# Power.net
KiCad netlist of a schematic drawn in Altium Designer
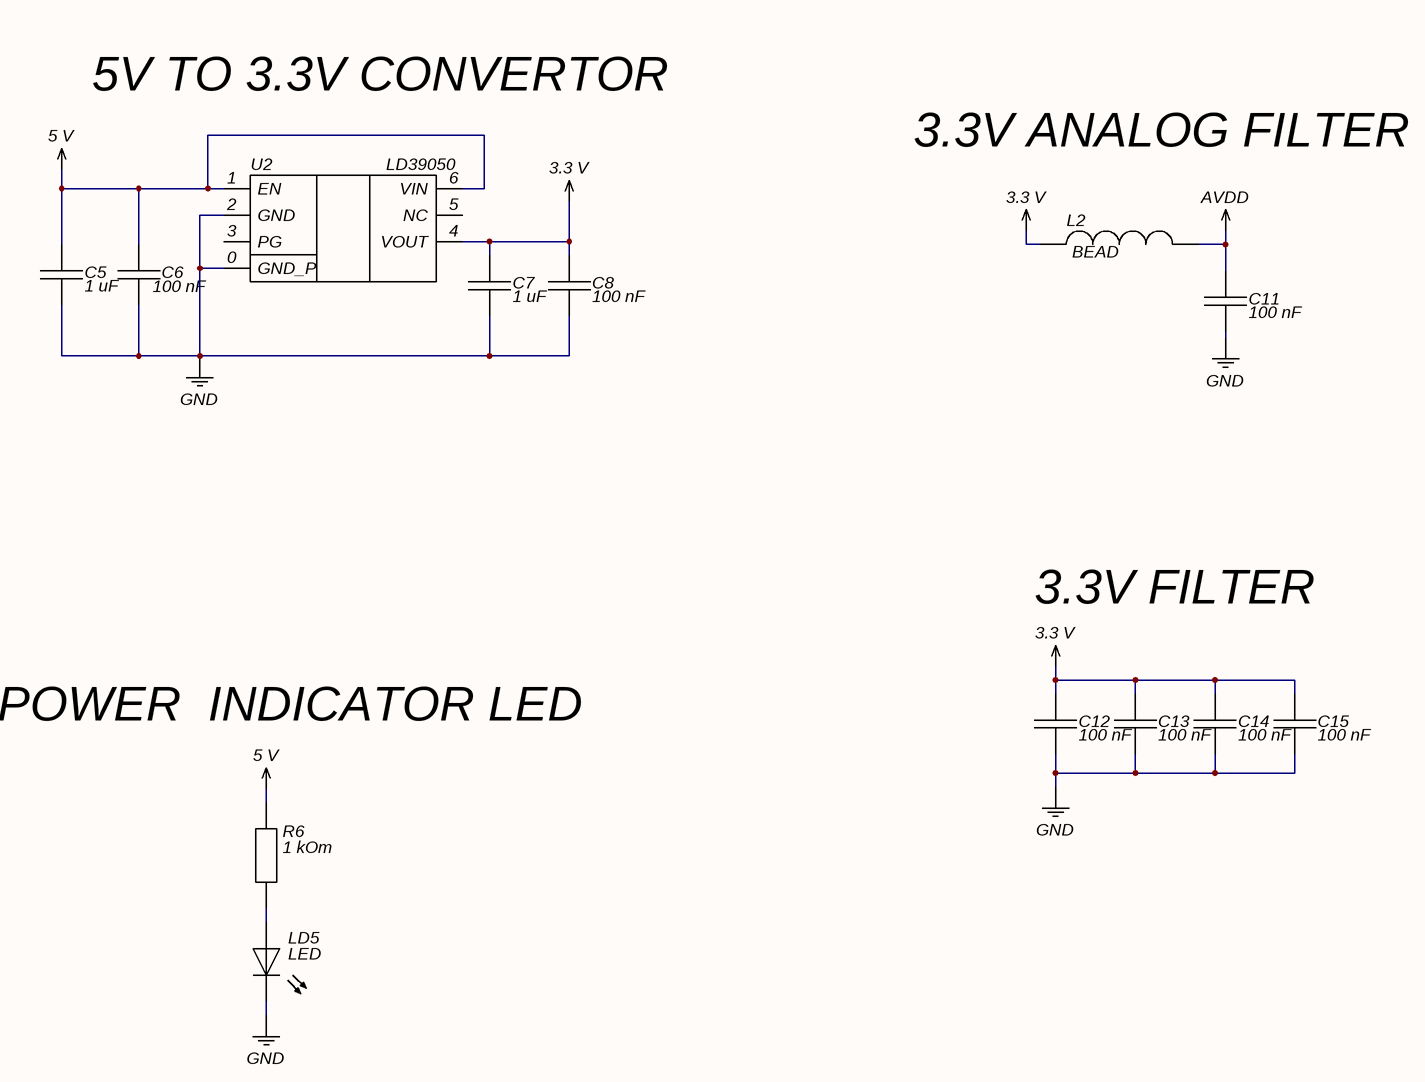
[diagram p0: Power.SchDoc]

(export (version "E")
  (design (tool "Eeschema 10.0.6"))
  (components
    (comp (ref "C5") (value "1 uF") (footprint "0603") (libsource (lib "MyLib") (part "Cup")))
    (comp (ref "C6") (value "100 nF") (footprint "0603") (libsource (lib "MyLib") (part "Cup")))
    (comp (ref "C7") (value "1 uF") (footprint "0603") (libsource (lib "MyLib") (part "Cup")))
    (comp (ref "C8") (value "100 nF") (footprint "0603") (libsource (lib "MyLib") (part "Cup")))
    (comp (ref "C11") (value "100 nF") (footprint "0603") (libsource (lib "MyLib") (part "Cup")))
    (comp (ref "C12") (value "100 nF") (footprint "0603") (libsource (lib "MyLib") (part "Cup")))
    (comp (ref "C13") (value "100 nF") (footprint "0603") (libsource (lib "MyLib") (part "Cup")))
    (comp (ref "C14") (value "100 nF") (footprint "0603") (libsource (lib "MyLib") (part "Cup")))
    (comp (ref "C15") (value "100 nF") (footprint "0603") (libsource (lib "MyLib") (part "Cup")))
    (comp (ref "L2") (value "100 mH") (footprint "0603") (libsource (lib "MyLib") (part "Inductor")))
    (comp (ref "LD5") (value "LED") (footprint "0603") (libsource (lib "MyLib") (part "LED")))
    (comp (ref "R6") (value "1 kOm") (footprint "0603") (libsource (lib "MyLib") (part "Res")))
    (comp (ref "U2")
      (value "LD39050")
      (footprint "DFN6")
      (description "voltage regulator")
      (libsource (lib "ECard_Lib") (part "LD39050"))
    )
  )
  (nets
    (net (code "1") (name "3.3 V") (class "Default")
      (node (ref "C12") (pin "2") (pinfunction "2_2") (pintype "passive"))
      (node (ref "C13") (pin "2") (pinfunction "2_2") (pintype "passive"))
      (node (ref "C14") (pin "2") (pinfunction "2_2") (pintype "passive"))
      (node (ref "C15") (pin "2") (pinfunction "2_2") (pintype "passive"))
      (node (ref "C7") (pin "1") (pinfunction "1_1") (pintype "passive"))
      (node (ref "C8") (pin "1") (pinfunction "1_1") (pintype "passive"))
      (node (ref "L2") (pin "1") (pinfunction "1_1") (pintype "passive"))
      (node (ref "U2") (pin "4") (pinfunction "VOUT_4") (pintype "passive"))
    )
    (net (code "2") (name "5 V") (class "Default")
      (node (ref "C5") (pin "1") (pinfunction "1_1") (pintype "passive"))
      (node (ref "C6") (pin "1") (pinfunction "1_1") (pintype "passive"))
      (node (ref "R6") (pin "2") (pinfunction "2_2") (pintype "passive"))
      (node (ref "U2") (pin "1") (pinfunction "EN_1") (pintype "passive"))
      (node (ref "U2") (pin "6") (pinfunction "VIN_6") (pintype "passive"))
    )
    (net (code "3") (name "AVDD") (class "Default")
      (node (ref "C11") (pin "2") (pinfunction "2_2") (pintype "passive"))
      (node (ref "L2") (pin "2") (pinfunction "2_2") (pintype "passive"))
    )
    (net (code "4") (name "GND") (class "Default")
      (node (ref "C11") (pin "1") (pinfunction "1_1") (pintype "passive"))
      (node (ref "C12") (pin "1") (pinfunction "1_1") (pintype "passive"))
      (node (ref "C13") (pin "1") (pinfunction "1_1") (pintype "passive"))
      (node (ref "C14") (pin "1") (pinfunction "1_1") (pintype "passive"))
      (node (ref "C15") (pin "1") (pinfunction "1_1") (pintype "passive"))
      (node (ref "C5") (pin "2") (pinfunction "2_2") (pintype "passive"))
      (node (ref "C6") (pin "2") (pinfunction "2_2") (pintype "passive"))
      (node (ref "C7") (pin "2") (pinfunction "2_2") (pintype "passive"))
      (node (ref "C8") (pin "2") (pinfunction "2_2") (pintype "passive"))
      (node (ref "LD5") (pin "2") (pinfunction "2_2") (pintype "passive"))
      (node (ref "U2") (pin "0") (pinfunction "GND_P_0") (pintype "passive"))
      (node (ref "U2") (pin "2") (pinfunction "GND_2") (pintype "passive"))
    )
    (net (code "5") (name "Net-(LD5-2-Pad1)") (class "Default")
      (node (ref "LD5") (pin "1") (pinfunction "2_1") (pintype "passive"))
      (node (ref "R6") (pin "1") (pinfunction "1_1") (pintype "passive"))
    )
    (net (code "6") (name "unconnected-(U2-NC-Pad5)") (class "Default")
      (node (ref "U2") (pin "5") (pinfunction "NC_5") (pintype "passive"))
    )
    (net (code "7") (name "unconnected-(U2-PG-Pad3)") (class "Default")
      (node (ref "U2") (pin "3") (pinfunction "PG_3") (pintype "passive"))
    )
  )
)
